# Sheet2.net
KiCad netlist of a schematic drawn in Altium Designer
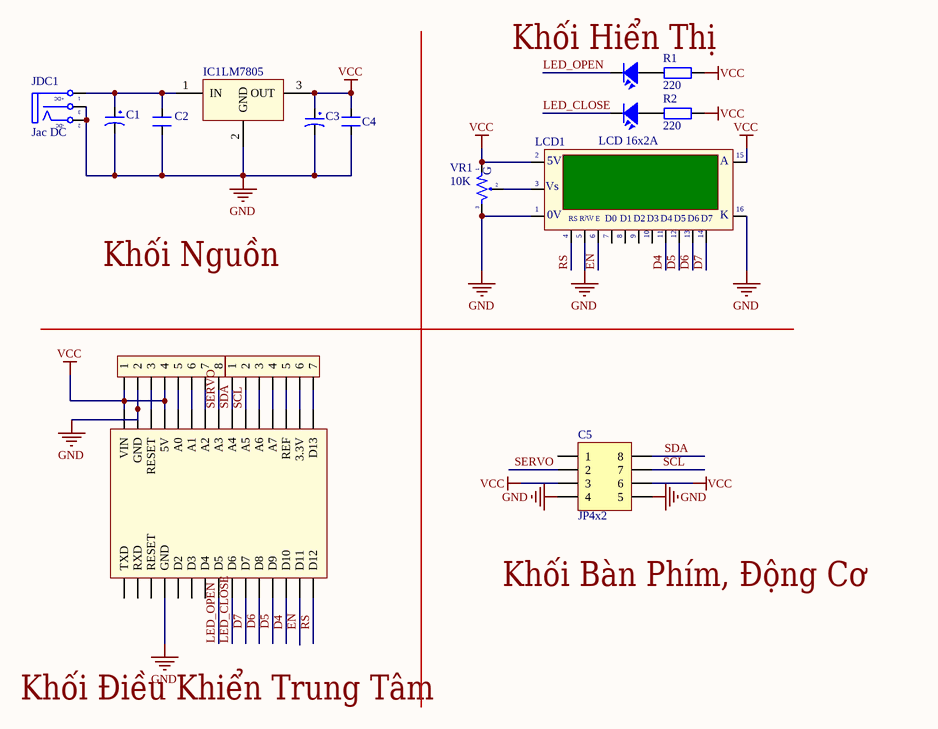
[diagram p0: Sheet2.SchDoc]

(export (version "E")
  (design (tool "Eeschema 10.0.6"))
  (components
    (comp (ref "*1")
      (value "arduinoNano")
      (footprint "Arduino nano")
      (libsource (lib "DEV_lib") (part "arduinoNano"))
    )
    (comp (ref "C1")
      (value "1000uF/16V")
      (footprint "CP1.5/3.4")
      (description "Cap 1000uF/16V - 220uF/50V")
      (libsource (lib "syhaunguyen") (part "CP4"))
    )
    (comp (ref "C2")
      (value "100pF")
      (footprint "CN1")
      (description "Cap np  1pF - 472pF")
      (libsource (lib "DEV_lib") (part "CN1"))
    )
    (comp (ref "C3")
      (value "1000uF/16V")
      (footprint "CP1.5/3.4")
      (description "Cap 1000uF/16V - 220uF/50V")
      (libsource (lib "syhaunguyen") (part "CP4"))
    )
    (comp (ref "C4")
      (value "100pF")
      (footprint "CN1")
      (description "Cap np  1pF - 472pF")
      (libsource (lib "DEV_lib") (part "CN1"))
    )
    (comp (ref "C5")
      (value "JP4x2")
      (footprint "JP4-D2C")
      (description "WR-PHD 2.54 mm Dual Socket Header")
      (fields
        (field (name "MANUFACTURER") "Würth Elektronik eiSos GmbH")
        (field (name "PARTNO") "61300821821")
        (field (name "CREATED BY") "Karrer Zheng")
      )
      (libsource (lib "LIBRARY") (part "JP4x2"))
    )
    (comp (ref "IC1")
      (value "LM7805")
      (footprint "QTO-220")
      (description "On ap +, from + 5 to + 24VDC")
      (libsource (lib "DEV_lib") (part "LM78xx"))
    )
    (comp (ref "JDC1")
      (value "Jac DC")
      (footprint "DC-IN")
      (description "Jac DC input")
      (libsource (lib "syhaunguyen") (part "DCIN"))
    )
    (comp (ref "JP1") (value "JP8 PIN") (footprint "JP8") (libsource (lib "syhaunguyen") (part "JP8")))
    (comp (ref "JP2") (value "JP7 PIN") (footprint "JP7") (libsource (lib "syhaunguyen") (part "JP7")))
    (comp (ref "LCD1")
      (value "LCD 16x2A")
      (footprint "LCD16X2N")
      (description "LCD dipslay 16 char, 2 line")
      (libsource (lib "LIBRARY") (part "LCD16x2A"))
    )
    (comp (ref "LED1")
      (value "LED")
      (footprint "LED-5-Green")
      (description "LED Single colour Green and Red")
      (libsource (lib "syhaunguyen") (part "LED"))
    )
    (comp (ref "LED2")
      (value "LED")
      (footprint "LED-5-RED")
      (description "LED Single colour Green and Red")
      (libsource (lib "syhaunguyen") (part "LED"))
    )
    (comp (ref "R1")
      (value "220")
      (footprint "R1/4W")
      (description "Resistor 1/4W")
      (libsource (lib "syhaunguyen") (part "R1/4W"))
    )
    (comp (ref "R2")
      (value "220")
      (footprint "R1/4W")
      (description "Resistor 1/4W")
      (libsource (lib "syhaunguyen") (part "R1/4W"))
    )
    (comp (ref "VR1")
      (value "10K")
      (footprint "VR-S2")
      (description "Var Resistor")
      (libsource (lib "LIBRARY") (part "VR-S"))
    )
  )
  (nets
    (net (code "1") (name "/D4") (class "Default")
      (node (ref "*1") (pin "13") (pinfunction "D10_13") (pintype "passive"))
      (node (ref "LCD1") (pin "11") (pinfunction "D4_11") (pintype "passive"))
    )
    (net (code "2") (name "/D5") (class "Default")
      (node (ref "*1") (pin "12") (pinfunction "D9_12") (pintype "passive"))
      (node (ref "LCD1") (pin "12") (pinfunction "D5_12") (pintype "passive"))
    )
    (net (code "3") (name "/D6") (class "Default")
      (node (ref "*1") (pin "11") (pinfunction "D8_11") (pintype "passive"))
      (node (ref "LCD1") (pin "13") (pinfunction "D6_13") (pintype "passive"))
    )
    (net (code "4") (name "/D7") (class "Default")
      (node (ref "*1") (pin "10") (pinfunction "D7_10") (pintype "passive"))
      (node (ref "LCD1") (pin "14") (pinfunction "D7_14") (pintype "passive"))
    )
    (net (code "5") (name "/EN") (class "Default")
      (node (ref "*1") (pin "14") (pinfunction "D11_14") (pintype "passive"))
      (node (ref "LCD1") (pin "6") (pinfunction "~{EN}_6") (pintype "passive"))
    )
    (net (code "10") (name "/LED_CLOSE") (class "Default")
      (node (ref "*1") (pin "9") (pinfunction "D6_9") (pintype "passive"))
      (node (ref "LED2") (pin "2") (pinfunction "2_2") (pintype "passive"))
    )
    (net (code "11") (name "/LED_OPEN") (class "Default")
      (node (ref "*1") (pin "8") (pinfunction "D5_8") (pintype "passive"))
      (node (ref "LED1") (pin "2") (pinfunction "2_2") (pintype "passive"))
    )
    (net (code "12") (name "/RS") (class "Default")
      (node (ref "*1") (pin "15") (pinfunction "D12_15") (pintype "passive"))
      (node (ref "LCD1") (pin "4") (pinfunction "RS_4") (pintype "passive"))
    )
    (net (code "13") (name "/SCL") (class "Default")
      (node (ref "*1") (pin "21") (pinfunction "A5_21") (pintype "passive"))
      (node (ref "C5") (pin "7") (pinfunction "7_7") (pintype "passive"))
      (node (ref "JP2") (pin "2") (pinfunction "2_2") (pintype "passive"))
    )
    (net (code "14") (name "/SDA") (class "Default")
      (node (ref "*1") (pin "22") (pinfunction "A4_22") (pintype "passive"))
      (node (ref "C5") (pin "8") (pinfunction "8_8") (pintype "passive"))
      (node (ref "JP2") (pin "1") (pinfunction "1_1") (pintype "passive"))
    )
    (net (code "15") (name "/SERVO") (class "Default")
      (node (ref "*1") (pin "23") (pinfunction "A3_23") (pintype "passive"))
      (node (ref "C5") (pin "2") (pinfunction "2_2") (pintype "passive"))
      (node (ref "JP1") (pin "8") (pinfunction "8_8") (pintype "passive"))
    )
    (net (code "16") (name "GND") (class "Default")
      (node (ref "*1") (pin "29") (pinfunction "GND_29") (pintype "passive"))
      (node (ref "*1") (pin "4") (pinfunction "GND_4") (pintype "passive"))
      (node (ref "C1") (pin "2") (pinfunction "2_2") (pintype "passive"))
      (node (ref "C2") (pin "1") (pinfunction "1_1") (pintype "passive"))
      (node (ref "C3") (pin "2") (pinfunction "2_2") (pintype "passive"))
      (node (ref "C4") (pin "1") (pinfunction "1_1") (pintype "passive"))
      (node (ref "C5") (pin "4") (pinfunction "4_4") (pintype "passive"))
      (node (ref "C5") (pin "5") (pinfunction "5_5") (pintype "passive"))
      (node (ref "IC1") (pin "2") (pinfunction "GND_2") (pintype "passive"))
      (node (ref "JDC1") (pin "2") (pinfunction "TN_2") (pintype "passive"))
      (node (ref "JDC1") (pin "3") (pinfunction "S_3") (pintype "power_in"))
      (node (ref "JP1") (pin "2") (pinfunction "2_2") (pintype "passive"))
      (node (ref "LCD1") (pin "1") (pinfunction "GND_1") (pintype "passive"))
      (node (ref "LCD1") (pin "16") (pinfunction "K_16") (pintype "passive"))
      (node (ref "LCD1") (pin "5") (pinfunction "R/~{W}_5") (pintype "passive"))
      (node (ref "VR1") (pin "3") (pinfunction "3_3") (pintype "passive"))
    )
    (net (code "17") (name "Net-(*1-3.3V)") (class "Default")
      (node (ref "*1") (pin "17") (pinfunction "3.3V_17") (pintype "passive"))
      (node (ref "JP2") (pin "6") (pinfunction "6_6") (pintype "passive"))
    )
    (net (code "18") (name "Net-(*1-A0)") (class "Default")
      (node (ref "*1") (pin "26") (pinfunction "A0_26") (pintype "passive"))
      (node (ref "JP1") (pin "5") (pinfunction "5_5") (pintype "passive"))
    )
    (net (code "19") (name "Net-(*1-A1)") (class "Default")
      (node (ref "*1") (pin "25") (pinfunction "A1_25") (pintype "passive"))
      (node (ref "JP1") (pin "6") (pinfunction "6_6") (pintype "passive"))
    )
    (net (code "20") (name "Net-(*1-A2)") (class "Default")
      (node (ref "*1") (pin "24") (pinfunction "A2_24") (pintype "passive"))
      (node (ref "JP1") (pin "7") (pinfunction "7_7") (pintype "passive"))
    )
    (net (code "21") (name "Net-(*1-A6)") (class "Default")
      (node (ref "*1") (pin "20") (pinfunction "A6_20") (pintype "passive"))
      (node (ref "JP2") (pin "3") (pinfunction "3_3") (pintype "passive"))
    )
    (net (code "22") (name "Net-(*1-A7)") (class "Default")
      (node (ref "*1") (pin "19") (pinfunction "A7_19") (pintype "passive"))
      (node (ref "JP2") (pin "4") (pinfunction "4_4") (pintype "passive"))
    )
    (net (code "23") (name "Net-(*1-D13)") (class "Default")
      (node (ref "*1") (pin "16") (pinfunction "D13_16") (pintype "passive"))
      (node (ref "JP2") (pin "7") (pinfunction "7_7") (pintype "passive"))
    )
    (net (code "24") (name "Net-(*1-REF)") (class "Default")
      (node (ref "*1") (pin "18") (pinfunction "REF_18") (pintype "passive"))
      (node (ref "JP2") (pin "5") (pinfunction "5_5") (pintype "passive"))
    )
    (net (code "25") (name "Net-(*1-RESET-Pad28)") (class "Default")
      (node (ref "*1") (pin "28") (pinfunction "RESET_28") (pintype "passive"))
      (node (ref "JP1") (pin "3") (pinfunction "3_3") (pintype "passive"))
    )
    (net (code "26") (name "Net-(IC1-IN)") (class "Default")
      (node (ref "C1") (pin "1") (pinfunction "1_1") (pintype "passive"))
      (node (ref "C2") (pin "2") (pinfunction "2_2") (pintype "passive"))
      (node (ref "IC1") (pin "1") (pinfunction "IN_1") (pintype "passive"))
      (node (ref "JDC1") (pin "1") (pinfunction "T_1") (pintype "passive"))
    )
    (net (code "27") (name "Net-(LCD1-VEE)") (class "Default")
      (node (ref "LCD1") (pin "3") (pinfunction "VEE_3") (pintype "passive"))
      (node (ref "VR1") (pin "2") (pinfunction "2_2") (pintype "passive"))
    )
    (net (code "28") (name "Net-(LED1-Pad1)") (class "Default")
      (node (ref "LED1") (pin "1") (pinfunction "1_1") (pintype "passive"))
      (node (ref "R1") (pin "1") (pinfunction "1_1") (pintype "passive"))
    )
    (net (code "29") (name "Net-(LED2-Pad1)") (class "Default")
      (node (ref "LED2") (pin "1") (pinfunction "1_1") (pintype "passive"))
      (node (ref "R2") (pin "1") (pinfunction "1_1") (pintype "passive"))
    )
    (net (code "30") (name "VCC") (class "Default")
      (node (ref "*1") (pin "27") (pinfunction "5V_27") (pintype "passive"))
      (node (ref "*1") (pin "30") (pinfunction "VIN_30") (pintype "passive"))
      (node (ref "C3") (pin "1") (pinfunction "1_1") (pintype "passive"))
      (node (ref "C4") (pin "2") (pinfunction "2_2") (pintype "passive"))
      (node (ref "C5") (pin "3") (pinfunction "3_3") (pintype "passive"))
      (node (ref "C5") (pin "6") (pinfunction "6_6") (pintype "passive"))
      (node (ref "IC1") (pin "3") (pinfunction "OUT_3") (pintype "passive"))
      (node (ref "JP1") (pin "1") (pinfunction "1_1") (pintype "passive"))
      (node (ref "JP1") (pin "4") (pinfunction "4_4") (pintype "passive"))
      (node (ref "LCD1") (pin "15") (pinfunction "A_15") (pintype "passive"))
      (node (ref "LCD1") (pin "2") (pinfunction "VDD_2") (pintype "passive"))
      (node (ref "R1") (pin "2") (pinfunction "2_2") (pintype "passive"))
      (node (ref "R2") (pin "2") (pinfunction "2_2") (pintype "passive"))
      (node (ref "VR1") (pin "1") (pinfunction "1_1") (pintype "passive"))
    )
    (net (code "31") (name "unconnected-(*1-D2-Pad5)") (class "Default")
      (node (ref "*1") (pin "5") (pinfunction "D2_5") (pintype "passive"))
    )
    (net (code "32") (name "unconnected-(*1-D3-Pad6)") (class "Default")
      (node (ref "*1") (pin "6") (pinfunction "D3_6") (pintype "passive"))
    )
    (net (code "33") (name "unconnected-(*1-D4-Pad7)") (class "Default")
      (node (ref "*1") (pin "7") (pinfunction "D4_7") (pintype "passive"))
    )
    (net (code "34") (name "unconnected-(*1-RESET-Pad3)") (class "Default")
      (node (ref "*1") (pin "3") (pinfunction "RESET_3") (pintype "passive"))
    )
    (net (code "35") (name "unconnected-(*1-RXD-Pad2)") (class "Default")
      (node (ref "*1") (pin "2") (pinfunction "RXD_2") (pintype "passive"))
    )
    (net (code "36") (name "unconnected-(*1-TXD-Pad1)") (class "Default")
      (node (ref "*1") (pin "1") (pinfunction "TXD_1") (pintype "passive"))
    )
    (net (code "37") (name "unconnected-(C5-Pad1)") (class "Default")
      (node (ref "C5") (pin "1") (pinfunction "1_1") (pintype "passive"))
    )
    (net (code "38") (name "unconnected-(LCD1-D0-Pad7)") (class "Default")
      (node (ref "LCD1") (pin "7") (pinfunction "D0_7") (pintype "passive"))
    )
    (net (code "39") (name "unconnected-(LCD1-D1-Pad8)") (class "Default")
      (node (ref "LCD1") (pin "8") (pinfunction "D1_8") (pintype "passive"))
    )
    (net (code "40") (name "unconnected-(LCD1-D2-Pad9)") (class "Default")
      (node (ref "LCD1") (pin "9") (pinfunction "D2_9") (pintype "passive"))
    )
    (net (code "41") (name "unconnected-(LCD1-D3-Pad10)") (class "Default")
      (node (ref "LCD1") (pin "10") (pinfunction "D3_10") (pintype "passive"))
    )
  )
)
